# tqfp-sandwich.net
KiCad netlist of a schematic drawn in EAGLE
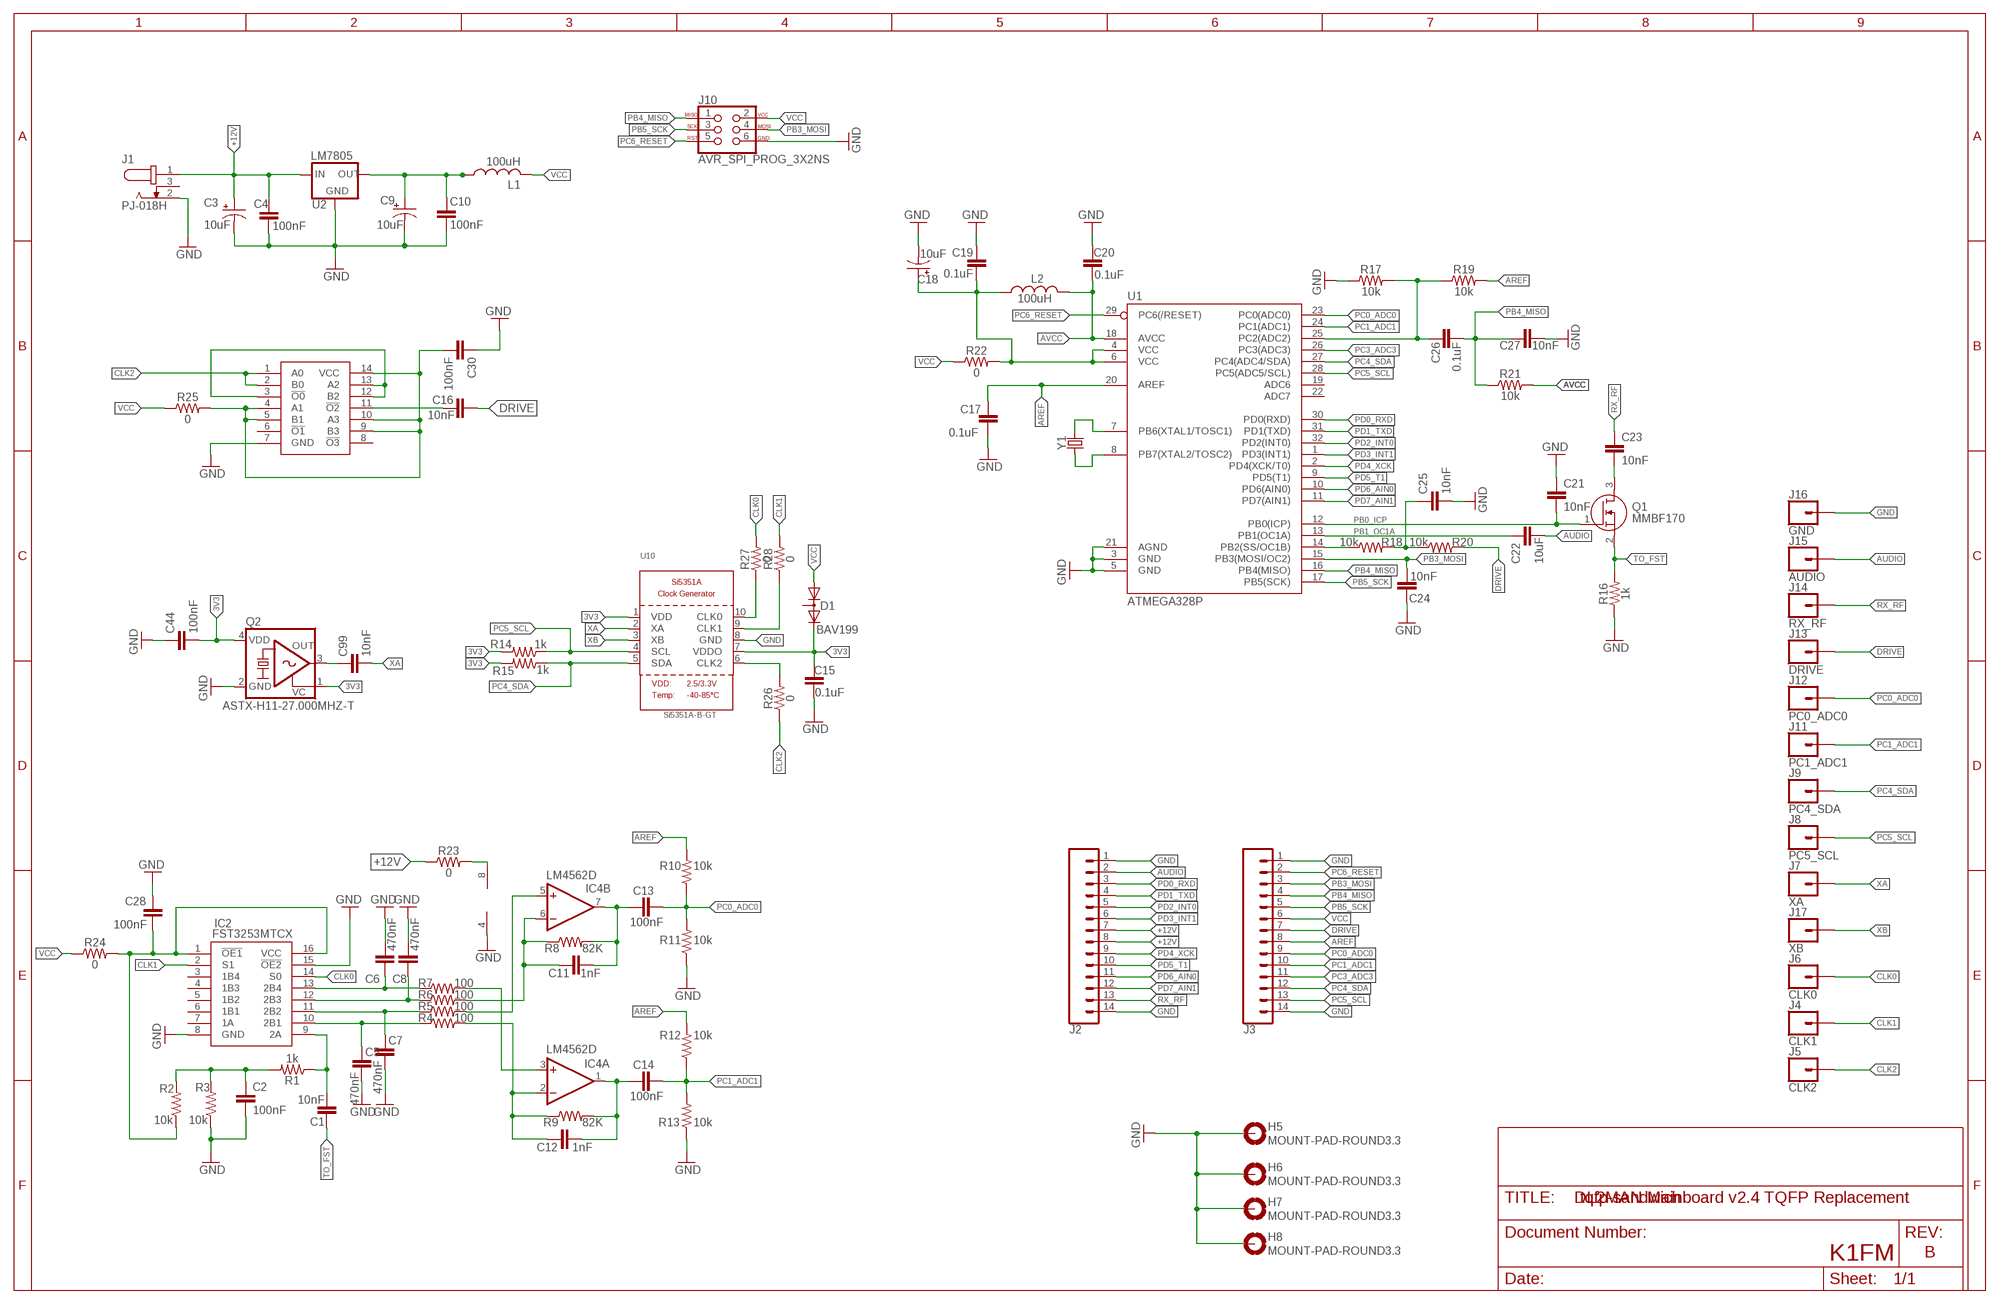
[diagram p0: schematic, sheet 1]

(export (version "E")
  (design (tool "Eeschema 10.0.6"))
  (components
    (comp (ref "C1")
      (value "10nF")
      (footprint "eagle-import:0603")
      (libsource (lib "eagle-import") (part "10NF-0603-50V-10%"))
    )
    (comp (ref "C2")
      (value "100nF")
      (footprint "eagle-import:0603")
      (libsource (lib "eagle-import") (part "10NF-0603-50V-10%"))
    )
    (comp (ref "C3")
      (value "10uF")
      (footprint "eagle-import:EIA3216")
      (libsource (lib "eagle-import") (part "10UF-POLAR-EIA3216-16V-10%(TANT)"))
    )
    (comp (ref "C4")
      (value "100nF")
      (footprint "eagle-import:0603")
      (libsource (lib "eagle-import") (part "10NF-0603-50V-10%"))
    )
    (comp (ref "C5")
      (value "470nF")
      (footprint "eagle-import:0603")
      (libsource (lib "eagle-import") (part "470PF-0603-50V-5%"))
    )
    (comp (ref "C6")
      (value "470nF")
      (footprint "eagle-import:0603")
      (libsource (lib "eagle-import") (part "470PF-0603-50V-5%"))
    )
    (comp (ref "C7")
      (value "470nF")
      (footprint "eagle-import:0603")
      (libsource (lib "eagle-import") (part "470PF-0603-50V-5%"))
    )
    (comp (ref "C8")
      (value "470nF")
      (footprint "eagle-import:0603")
      (libsource (lib "eagle-import") (part "470PF-0603-50V-5%"))
    )
    (comp (ref "C9")
      (value "10uF")
      (footprint "eagle-import:EIA3216")
      (libsource (lib "eagle-import") (part "10UF-POLAR-EIA3216-16V-10%(TANT)"))
    )
    (comp (ref "C10")
      (value "100nF")
      (footprint "eagle-import:0603")
      (libsource (lib "eagle-import") (part "10NF-0603-50V-10%"))
    )
    (comp (ref "C11")
      (value "1nF")
      (footprint "eagle-import:0603")
      (libsource (lib "eagle-import") (part "1.0NF/1000PF-0603-50V-10%"))
    )
    (comp (ref "C12")
      (value "1nF")
      (footprint "eagle-import:0603")
      (libsource (lib "eagle-import") (part "1.0NF/1000PF-0603-50V-10%"))
    )
    (comp (ref "C13")
      (value "100nF")
      (footprint "eagle-import:0603")
      (libsource (lib "eagle-import") (part "10NF-0603-50V-10%"))
    )
    (comp (ref "C14")
      (value "100nF")
      (footprint "eagle-import:0603")
      (libsource (lib "eagle-import") (part "10NF-0603-50V-10%"))
    )
    (comp (ref "C15")
      (value "0.1uF")
      (footprint "eagle-import:0603")
      (libsource (lib "eagle-import") (part "0.1UF-0603-25V-(+80/-20%)"))
    )
    (comp (ref "C16")
      (value "10nF")
      (footprint "eagle-import:0603")
      (libsource (lib "eagle-import") (part "10NF-0603-50V-10%"))
    )
    (comp (ref "C17")
      (value "0.1uF")
      (footprint "eagle-import:0603")
      (libsource (lib "eagle-import") (part "0.1UF-0603-25V-(+80/-20%)"))
    )
    (comp (ref "C18")
      (value "10uF")
      (footprint "eagle-import:EIA3216")
      (libsource (lib "eagle-import") (part "10UF-POLAR-EIA3216-16V-10%(TANT)"))
    )
    (comp (ref "C19")
      (value "0.1uF")
      (footprint "eagle-import:0603")
      (libsource (lib "eagle-import") (part "0.1UF-0603-25V-(+80/-20%)"))
    )
    (comp (ref "C20")
      (value "0.1uF")
      (footprint "eagle-import:0603")
      (libsource (lib "eagle-import") (part "0.1UF-0603-25V-(+80/-20%)"))
    )
    (comp (ref "C21")
      (value "10nF")
      (footprint "eagle-import:0603")
      (libsource (lib "eagle-import") (part "10NF-0603-50V-10%"))
    )
    (comp (ref "C22")
      (value "10uF")
      (footprint "eagle-import:0603")
      (libsource (lib "eagle-import") (part "10UF-0603-6.3V-20%"))
    )
    (comp (ref "C23")
      (value "10nF")
      (footprint "eagle-import:0603")
      (libsource (lib "eagle-import") (part "10NF-0603-50V-10%"))
    )
    (comp (ref "C24")
      (value "10nF")
      (footprint "eagle-import:0603")
      (libsource (lib "eagle-import") (part "10NF-0603-50V-10%"))
    )
    (comp (ref "C25")
      (value "10nF")
      (footprint "eagle-import:0603")
      (libsource (lib "eagle-import") (part "10NF-0603-50V-10%"))
    )
    (comp (ref "C26")
      (value "0.1uF")
      (footprint "eagle-import:0603")
      (libsource (lib "eagle-import") (part "0.1UF-0603-25V-(+80/-20%)"))
    )
    (comp (ref "C27")
      (value "10nF")
      (footprint "eagle-import:0603")
      (libsource (lib "eagle-import") (part "10NF-0603-50V-10%"))
    )
    (comp (ref "C28")
      (value "100nF")
      (footprint "eagle-import:0603")
      (libsource (lib "eagle-import") (part "10NF-0603-50V-10%"))
    )
    (comp (ref "C30")
      (value "100nF")
      (footprint "eagle-import:0603")
      (libsource (lib "eagle-import") (part "10NF-0603-50V-10%"))
    )
    (comp (ref "C44")
      (value "100nF")
      (footprint "eagle-import:0603")
      (libsource (lib "eagle-import") (part "10NF-0603-50V-10%"))
    )
    (comp (ref "C99")
      (value "10nF")
      (footprint "eagle-import:0603")
      (libsource (lib "eagle-import") (part "10NF-0603-50V-10%"))
    )
    (comp (ref "D1")
      (value "BAV199")
      (footprint "eagle-import:SOT23")
      (libsource (lib "eagle-import") (part "BAV199"))
    )
    (comp (ref "H5")
      (value "MOUNT-PAD-ROUND3.3")
      (footprint "eagle-import:3,3-PAD")
      (libsource (lib "eagle-import") (part "MOUNT-PAD-ROUND3.3"))
    )
    (comp (ref "H6")
      (value "MOUNT-PAD-ROUND3.3")
      (footprint "eagle-import:3,3-PAD")
      (libsource (lib "eagle-import") (part "MOUNT-PAD-ROUND3.3"))
    )
    (comp (ref "H7")
      (value "MOUNT-PAD-ROUND3.3")
      (footprint "eagle-import:3,3-PAD")
      (libsource (lib "eagle-import") (part "MOUNT-PAD-ROUND3.3"))
    )
    (comp (ref "H8")
      (value "MOUNT-PAD-ROUND3.3")
      (footprint "eagle-import:3,3-PAD")
      (libsource (lib "eagle-import") (part "MOUNT-PAD-ROUND3.3"))
    )
    (comp (ref "IC2")
      (value "FST3253MTCX")
      (footprint "eagle-import:SOP65P640X110-16N")
      (fields (field (name "MOUSER_PART_NUMBER") "512-FST3253MTCX"))
      (libsource (lib "eagle-import") (part "FST3253MTCX"))
    )
    (comp (ref "IC3")
      (value "74ACT00MTC")
      (footprint "eagle-import:SOP65P640X120-14N")
      (fields (field (name "MOUSER_PART_NUMBER") "512-74ACT00MTC"))
      (libsource (lib "eagle-import") (part "74ACT00MTC"))
    )
    (comp (ref "IC4")
      (value "LM4562D")
      (footprint "eagle-import:SO08")
      (libsource (lib "eagle-import") (part "LM4562D"))
    )
    (comp (ref "J1")
      (value "PJ-018H")
      (footprint "eagle-import:CUI_PJ-018H")
      (fields (field (name "MANUFACTURER") "CUI INC"))
      (libsource (lib "eagle-import") (part "PJ-018H"))
    )
    (comp (ref "J2")
      (value "CONN_14")
      (footprint "eagle-import:1X14")
      (libsource (lib "eagle-import") (part "CONN_14"))
    )
    (comp (ref "J3")
      (value "CONN_14")
      (footprint "eagle-import:1X14")
      (libsource (lib "eagle-import") (part "CONN_14"))
    )
    (comp (ref "J4")
      (value "CLK1")
      (footprint "eagle-import:1X01_LONGPAD")
      (libsource (lib "eagle-import") (part "CONN_01PTH_LONGPAD"))
    )
    (comp (ref "J5")
      (value "CLK2")
      (footprint "eagle-import:1X01_LONGPAD")
      (libsource (lib "eagle-import") (part "CONN_01PTH_LONGPAD"))
    )
    (comp (ref "J6")
      (value "CLK0")
      (footprint "eagle-import:1X01_LONGPAD")
      (libsource (lib "eagle-import") (part "CONN_01PTH_LONGPAD"))
    )
    (comp (ref "J7")
      (value "XA")
      (footprint "eagle-import:1X01_LONGPAD")
      (libsource (lib "eagle-import") (part "CONN_01PTH_LONGPAD"))
    )
    (comp (ref "J8")
      (value "PC5_SCL")
      (footprint "eagle-import:1X01_LONGPAD")
      (libsource (lib "eagle-import") (part "CONN_01PTH_LONGPAD"))
    )
    (comp (ref "J9")
      (value "PC4_SDA")
      (footprint "eagle-import:1X01_LONGPAD")
      (libsource (lib "eagle-import") (part "CONN_01PTH_LONGPAD"))
    )
    (comp (ref "J10")
      (value "AVR_SPI_PROG_3X2NS")
      (footprint "eagle-import:2X3-NS")
      (libsource (lib "eagle-import") (part "AVR_SPI_PROG_3X2NS"))
    )
    (comp (ref "J11")
      (value "PC1_ADC1")
      (footprint "eagle-import:1X01_LONGPAD")
      (libsource (lib "eagle-import") (part "CONN_01PTH_LONGPAD"))
    )
    (comp (ref "J12")
      (value "PC0_ADC0")
      (footprint "eagle-import:1X01_LONGPAD")
      (libsource (lib "eagle-import") (part "CONN_01PTH_LONGPAD"))
    )
    (comp (ref "J13")
      (value "DRIVE")
      (footprint "eagle-import:1X01_LONGPAD")
      (libsource (lib "eagle-import") (part "CONN_01PTH_LONGPAD"))
    )
    (comp (ref "J14")
      (value "RX_RF")
      (footprint "eagle-import:1X01_LONGPAD")
      (libsource (lib "eagle-import") (part "CONN_01PTH_LONGPAD"))
    )
    (comp (ref "J15")
      (value "AUDIO")
      (footprint "eagle-import:1X01_LONGPAD")
      (libsource (lib "eagle-import") (part "CONN_01PTH_LONGPAD"))
    )
    (comp (ref "J16")
      (value "GND")
      (footprint "eagle-import:1X01_LONGPAD")
      (libsource (lib "eagle-import") (part "CONN_01PTH_LONGPAD"))
    )
    (comp (ref "J17")
      (value "XB")
      (footprint "eagle-import:1X01_LONGPAD")
      (libsource (lib "eagle-import") (part "CONN_01PTH_LONGPAD"))
    )
    (comp (ref "L1")
      (value "100uH")
      (footprint "eagle-import:RESC0805_L")
      (libsource (lib "eagle-import") (part "INDUCTOR_0805_L"))
    )
    (comp (ref "L2")
      (value "100uH")
      (footprint "eagle-import:RESC0805_L")
      (libsource (lib "eagle-import") (part "INDUCTOR_0805_L"))
    )
    (comp (ref "Q1")
      (value "MMBF170")
      (footprint "eagle-import:SOT96P237X111-3N")
      (fields (field (name "MOUSER_PART_NUMBER") "512-MMBF170"))
      (libsource (lib "eagle-import") (part "MMBF170"))
    )
    (comp (ref "Q2")
      (value "ASTX-H11-27.000MHZ-T")
      (footprint "eagle-import:3.2X2.5_KXO-84")
      (libsource (lib "eagle-import") (part "KXO-VCXO-SINE-84"))
    )
    (comp (ref "R1")
      (value "1k")
      (footprint "eagle-import:0603")
      (libsource (lib "eagle-import") (part "1KOHM-0603-1/10W-1%"))
    )
    (comp (ref "R2")
      (value "10k")
      (footprint "eagle-import:0603")
      (libsource (lib "eagle-import") (part "10KOHM-0603-1/10W-1%"))
    )
    (comp (ref "R3")
      (value "10k")
      (footprint "eagle-import:0603")
      (libsource (lib "eagle-import") (part "10KOHM-0603-1/10W-1%"))
    )
    (comp (ref "R4")
      (value "100")
      (footprint "eagle-import:0603")
      (libsource (lib "eagle-import") (part "100OHM-0603-1/4W-5%"))
    )
    (comp (ref "R5")
      (value "100")
      (footprint "eagle-import:0603")
      (libsource (lib "eagle-import") (part "100OHM-0603-1/4W-5%"))
    )
    (comp (ref "R6")
      (value "100")
      (footprint "eagle-import:0603")
      (libsource (lib "eagle-import") (part "100OHM-0603-1/4W-5%"))
    )
    (comp (ref "R7")
      (value "100")
      (footprint "eagle-import:0603")
      (libsource (lib "eagle-import") (part "100OHM-0603-1/4W-5%"))
    )
    (comp (ref "R8")
      (value "82K")
      (footprint "eagle-import:0603")
      (libsource (lib "eagle-import") (part "82OHM-0603-1/10W-1%"))
    )
    (comp (ref "R9")
      (value "82K")
      (footprint "eagle-import:0603")
      (libsource (lib "eagle-import") (part "82OHM-0603-1/10W-1%"))
    )
    (comp (ref "R10")
      (value "10k")
      (footprint "eagle-import:0603")
      (libsource (lib "eagle-import") (part "10KOHM-0603-1/10W-1%"))
    )
    (comp (ref "R11")
      (value "10k")
      (footprint "eagle-import:0603")
      (libsource (lib "eagle-import") (part "10KOHM-0603-1/10W-1%"))
    )
    (comp (ref "R12")
      (value "10k")
      (footprint "eagle-import:0603")
      (libsource (lib "eagle-import") (part "10KOHM-0603-1/10W-1%"))
    )
    (comp (ref "R13")
      (value "10k")
      (footprint "eagle-import:0603")
      (libsource (lib "eagle-import") (part "10KOHM-0603-1/10W-1%"))
    )
    (comp (ref "R14")
      (value "1k")
      (footprint "eagle-import:0603")
      (libsource (lib "eagle-import") (part "1KOHM-0603-1/10W-1%"))
    )
    (comp (ref "R15")
      (value "1k")
      (footprint "eagle-import:0603")
      (libsource (lib "eagle-import") (part "1KOHM-0603-1/10W-1%"))
    )
    (comp (ref "R16")
      (value "1k")
      (footprint "eagle-import:0603")
      (libsource (lib "eagle-import") (part "1KOHM-0603-1/10W-1%"))
    )
    (comp (ref "R17")
      (value "10k")
      (footprint "eagle-import:0603")
      (libsource (lib "eagle-import") (part "10KOHM-0603-1/10W-1%"))
    )
    (comp (ref "R18")
      (value "10k")
      (footprint "eagle-import:0603")
      (libsource (lib "eagle-import") (part "10KOHM-0603-1/10W-1%"))
    )
    (comp (ref "R19")
      (value "10k")
      (footprint "eagle-import:0603")
      (libsource (lib "eagle-import") (part "10KOHM-0603-1/10W-1%"))
    )
    (comp (ref "R20")
      (value "10k")
      (footprint "eagle-import:0603")
      (libsource (lib "eagle-import") (part "10KOHM-0603-1/10W-1%"))
    )
    (comp (ref "R21")
      (value "10k")
      (footprint "eagle-import:0603")
      (libsource (lib "eagle-import") (part "10KOHM-0603-1/10W-1%"))
    )
    (comp (ref "R22")
      (value "0")
      (footprint "eagle-import:0603")
      (libsource (lib "eagle-import") (part "0OHM-0603-1/10W-5%"))
    )
    (comp (ref "R23")
      (value "0")
      (footprint "eagle-import:0603")
      (libsource (lib "eagle-import") (part "0OHM-0603-1/10W-5%"))
    )
    (comp (ref "R24")
      (value "0")
      (footprint "eagle-import:0603")
      (libsource (lib "eagle-import") (part "0OHM-0603-1/10W-5%"))
    )
    (comp (ref "R25")
      (value "0")
      (footprint "eagle-import:0603")
      (libsource (lib "eagle-import") (part "0OHM-0603-1/10W-5%"))
    )
    (comp (ref "R26")
      (value "0")
      (footprint "eagle-import:0603")
      (libsource (lib "eagle-import") (part "0OHM-0603-1/10W-5%"))
    )
    (comp (ref "R27")
      (value "0")
      (footprint "eagle-import:0603")
      (libsource (lib "eagle-import") (part "0OHM-0603-1/10W-5%"))
    )
    (comp (ref "R28")
      (value "0")
      (footprint "eagle-import:0603")
      (libsource (lib "eagle-import") (part "0OHM-0603-1/10W-5%"))
    )
    (comp (ref "U1")
      (value "ATMEGA328P")
      (footprint "eagle-import:TQFP32-08")
      (libsource (lib "eagle-import") (part "ATMEGA328P_TQFP"))
    )
    (comp (ref "U2")
      (value "LM7805")
      (footprint "eagle-import:TO-252")
      (libsource (lib "eagle-import") (part "V_REG_78XX7812"))
    )
    (comp (ref "U10")
      (value "Si5351A-B-GT")
      (footprint "eagle-import:MSOP10")
      (libsource (lib "eagle-import") (part "SI5351A"))
    )
    (comp (ref "Y1")
      (value "CRYSTALSMD-5X3.2-2PAD")
      (footprint "eagle-import:CRYSTAL-SMD-5X3.2-2PAD")
      (libsource (lib "eagle-import") (part "CRYSTALSMD-5X3.2-2PAD"))
    )
  )
  (nets
    (net (code "1") (name "+12V") (class "Default")
      (node (ref "C3") (pin "+") (pinfunction "+_+") (pintype "passive"))
      (node (ref "C4") (pin "2") (pinfunction "2_2") (pintype "passive"))
      (node (ref "J1") (pin "1") (pinfunction "1_1") (pintype "passive"))
      (node (ref "J2") (pin "7") (pinfunction "7_7") (pintype "passive"))
      (node (ref "J2") (pin "8") (pinfunction "8_8") (pintype "passive"))
      (node (ref "R23") (pin "1") (pinfunction "1_1") (pintype "passive"))
      (node (ref "U2") (pin "1") (pinfunction "IN_1") (pintype "input"))
    )
    (net (code "2") (name "/PB0_ICP") (class "Default")
      (node (ref "C21") (pin "2") (pinfunction "2_2") (pintype "passive"))
      (node (ref "Q1") (pin "1") (pinfunction "G_1") (pintype "bidirectional"))
      (node (ref "U1") (pin "12") (pinfunction "PB0(ICP)_12") (pintype "bidirectional"))
    )
    (net (code "3") (name "/PB1_OC1A") (class "Default")
      (node (ref "C22") (pin "1") (pinfunction "1_1") (pintype "passive"))
      (node (ref "U1") (pin "13") (pinfunction "PB1(OC1A)_13") (pintype "bidirectional"))
    )
    (net (code "4") (name "3V3") (class "Default")
      (node (ref "C15") (pin "2") (pinfunction "2_2") (pintype "passive"))
      (node (ref "C44") (pin "2") (pinfunction "2_2") (pintype "passive"))
      (node (ref "D1") (pin "2") (pinfunction "C_2") (pintype "passive"))
      (node (ref "Q2") (pin "1") (pinfunction "VC_1") (pintype "input"))
      (node (ref "Q2") (pin "4") (pinfunction "VDD_4") (pintype "power_in"))
      (node (ref "R14") (pin "2") (pinfunction "2_2") (pintype "passive"))
      (node (ref "R15") (pin "2") (pinfunction "2_2") (pintype "passive"))
      (node (ref "U10") (pin "1") (pinfunction "VDD_1") (pintype "power_in"))
      (node (ref "U10") (pin "7") (pinfunction "VDDO_7") (pintype "power_in"))
    )
    (net (code "5") (name "AREF") (class "Default")
      (node (ref "C17") (pin "2") (pinfunction "2_2") (pintype "passive"))
      (node (ref "J3") (pin "8") (pinfunction "8_8") (pintype "passive"))
      (node (ref "R10") (pin "2") (pinfunction "2_2") (pintype "passive"))
      (node (ref "R12") (pin "2") (pinfunction "2_2") (pintype "passive"))
      (node (ref "R19") (pin "2") (pinfunction "2_2") (pintype "passive"))
      (node (ref "U1") (pin "20") (pinfunction "AREF_20") (pintype "bidirectional"))
    )
    (net (code "6") (name "AUDIO") (class "Default")
      (node (ref "C22") (pin "2") (pinfunction "2_2") (pintype "passive"))
      (node (ref "J15") (pin "1") (pinfunction "1_1") (pintype "passive"))
      (node (ref "J2") (pin "2") (pinfunction "2_2") (pintype "passive"))
    )
    (net (code "7") (name "AVCC") (class "Default")
      (node (ref "C20") (pin "1") (pinfunction "1_1") (pintype "passive"))
      (node (ref "L2") (pin "2") (pinfunction "2_2") (pintype "passive"))
      (node (ref "R21") (pin "2") (pinfunction "2_2") (pintype "passive"))
      (node (ref "U1") (pin "18") (pinfunction "AVCC_18") (pintype "bidirectional"))
    )
    (net (code "8") (name "CLK0") (class "Default")
      (node (ref "IC2") (pin "14") (pinfunction "S0_14") (pintype "bidirectional"))
      (node (ref "J6") (pin "1") (pinfunction "1_1") (pintype "passive"))
      (node (ref "R27") (pin "2") (pinfunction "2_2") (pintype "passive"))
    )
    (net (code "9") (name "CLK1") (class "Default")
      (node (ref "IC2") (pin "2") (pinfunction "S1_2") (pintype "bidirectional"))
      (node (ref "J4") (pin "1") (pinfunction "1_1") (pintype "passive"))
      (node (ref "R28") (pin "2") (pinfunction "2_2") (pintype "passive"))
    )
    (net (code "10") (name "CLK2") (class "Default")
      (node (ref "IC3") (pin "1") (pinfunction "A0_1") (pintype "bidirectional"))
      (node (ref "IC3") (pin "2") (pinfunction "B0_2") (pintype "bidirectional"))
      (node (ref "J5") (pin "1") (pinfunction "1_1") (pintype "passive"))
      (node (ref "R26") (pin "1") (pinfunction "1_1") (pintype "passive"))
    )
    (net (code "11") (name "DRIVE") (class "Default")
      (node (ref "C16") (pin "2") (pinfunction "2_2") (pintype "passive"))
      (node (ref "J13") (pin "1") (pinfunction "1_1") (pintype "passive"))
      (node (ref "J3") (pin "7") (pinfunction "7_7") (pintype "passive"))
      (node (ref "R20") (pin "2") (pinfunction "2_2") (pintype "passive"))
    )
    (net (code "12") (name "GND") (class "Default")
      (node (ref "C10") (pin "1") (pinfunction "1_1") (pintype "passive"))
      (node (ref "C15") (pin "1") (pinfunction "1_1") (pintype "passive"))
      (node (ref "C17") (pin "1") (pinfunction "1_1") (pintype "passive"))
      (node (ref "C18") (pin "-") (pinfunction "-_-") (pintype "passive"))
      (node (ref "C19") (pin "2") (pinfunction "2_2") (pintype "passive"))
      (node (ref "C2") (pin "2") (pinfunction "2_2") (pintype "passive"))
      (node (ref "C20") (pin "2") (pinfunction "2_2") (pintype "passive"))
      (node (ref "C21") (pin "1") (pinfunction "1_1") (pintype "passive"))
      (node (ref "C24") (pin "1") (pinfunction "1_1") (pintype "passive"))
      (node (ref "C25") (pin "2") (pinfunction "2_2") (pintype "passive"))
      (node (ref "C27") (pin "2") (pinfunction "2_2") (pintype "passive"))
      (node (ref "C28") (pin "1") (pinfunction "1_1") (pintype "passive"))
      (node (ref "C3") (pin "-") (pinfunction "-_-") (pintype "passive"))
      (node (ref "C30") (pin "1") (pinfunction "1_1") (pintype "passive"))
      (node (ref "C4") (pin "1") (pinfunction "1_1") (pintype "passive"))
      (node (ref "C44") (pin "1") (pinfunction "1_1") (pintype "passive"))
      (node (ref "C5") (pin "2") (pinfunction "2_2") (pintype "passive"))
      (node (ref "C6") (pin "2") (pinfunction "2_2") (pintype "passive"))
      (node (ref "C7") (pin "2") (pinfunction "2_2") (pintype "passive"))
      (node (ref "C8") (pin "2") (pinfunction "2_2") (pintype "passive"))
      (node (ref "C9") (pin "-") (pinfunction "-_-") (pintype "passive"))
      (node (ref "H5") (pin "B3,3") (pinfunction "MOUNT_B3,3") (pintype "passive"))
      (node (ref "H6") (pin "B3,3") (pinfunction "MOUNT_B3,3") (pintype "passive"))
      (node (ref "H7") (pin "B3,3") (pinfunction "MOUNT_B3,3") (pintype "passive"))
      (node (ref "H8") (pin "B3,3") (pinfunction "MOUNT_B3,3") (pintype "passive"))
      (node (ref "IC2") (pin "15") (pinfunction "~{OE2}_15") (pintype "bidirectional"))
      (node (ref "IC2") (pin "8") (pinfunction "GND_8") (pintype "power_in"))
      (node (ref "IC3") (pin "7") (pinfunction "GND_7") (pintype "bidirectional"))
      (node (ref "IC4") (pin "4") (pinfunction "V-_4") (pintype "power_in"))
      (node (ref "J1") (pin "2") (pinfunction "2_2") (pintype "passive"))
      (node (ref "J10") (pin "6") (pinfunction "6_6") (pintype "passive"))
      (node (ref "J16") (pin "1") (pinfunction "1_1") (pintype "passive"))
      (node (ref "J2") (pin "1") (pinfunction "1_1") (pintype "passive"))
      (node (ref "J2") (pin "14") (pinfunction "14_14") (pintype "passive"))
      (node (ref "J3") (pin "1") (pinfunction "1_1") (pintype "passive"))
      (node (ref "J3") (pin "14") (pinfunction "14_14") (pintype "passive"))
      (node (ref "Q2") (pin "2") (pinfunction "GND_2") (pintype "power_in"))
      (node (ref "R11") (pin "1") (pinfunction "1_1") (pintype "passive"))
      (node (ref "R13") (pin "1") (pinfunction "1_1") (pintype "passive"))
      (node (ref "R16") (pin "1") (pinfunction "1_1") (pintype "passive"))
      (node (ref "R17") (pin "1") (pinfunction "1_1") (pintype "passive"))
      (node (ref "R3") (pin "1") (pinfunction "1_1") (pintype "passive"))
      (node (ref "U1") (pin "21") (pinfunction "AGND_21") (pintype "bidirectional"))
      (node (ref "U1") (pin "3") (pinfunction "GND_3") (pintype "bidirectional"))
      (node (ref "U1") (pin "5") (pinfunction "GND_5") (pintype "bidirectional"))
      (node (ref "U10") (pin "8") (pinfunction "GND_8") (pintype "power_in"))
      (node (ref "U2") (pin "3") (pinfunction "GND_3") (pintype "input"))
    )
    (net (code "13") (name "Net-(C2-Pad1)") (class "Default")
      (node (ref "C2") (pin "1") (pinfunction "1_1") (pintype "passive"))
      (node (ref "R1") (pin "2") (pinfunction "2_2") (pintype "passive"))
      (node (ref "R2") (pin "2") (pinfunction "2_2") (pintype "passive"))
      (node (ref "R3") (pin "2") (pinfunction "2_2") (pintype "passive"))
    )
    (net (code "14") (name "Net-(C18-Pad+)") (class "Default")
      (node (ref "C18") (pin "+") (pinfunction "+_+") (pintype "passive"))
      (node (ref "C19") (pin "1") (pinfunction "1_1") (pintype "passive"))
      (node (ref "L2") (pin "1") (pinfunction "1_1") (pintype "passive"))
      (node (ref "R22") (pin "2") (pinfunction "2_2") (pintype "passive"))
      (node (ref "U1") (pin "4") (pinfunction "VCC_4") (pintype "bidirectional"))
      (node (ref "U1") (pin "6") (pinfunction "VCC_6") (pintype "bidirectional"))
    )
    (net (code "15") (name "Net-(C25-Pad1)") (class "Default")
      (node (ref "C25") (pin "1") (pinfunction "1_1") (pintype "passive"))
      (node (ref "R18") (pin "2") (pinfunction "2_2") (pintype "passive"))
      (node (ref "R20") (pin "1") (pinfunction "1_1") (pintype "passive"))
    )
    (net (code "16") (name "Net-(IC2-2A)") (class "Default")
      (node (ref "C1") (pin "2") (pinfunction "2_2") (pintype "passive"))
      (node (ref "IC2") (pin "9") (pinfunction "2A_9") (pintype "bidirectional"))
      (node (ref "R1") (pin "1") (pinfunction "1_1") (pintype "passive"))
    )
    (net (code "17") (name "Net-(IC2-2B1)") (class "Default")
      (node (ref "C5") (pin "1") (pinfunction "1_1") (pintype "passive"))
      (node (ref "IC2") (pin "10") (pinfunction "2B1_10") (pintype "bidirectional"))
      (node (ref "R4") (pin "1") (pinfunction "1_1") (pintype "passive"))
    )
    (net (code "18") (name "Net-(IC2-2B2)") (class "Default")
      (node (ref "C7") (pin "1") (pinfunction "1_1") (pintype "passive"))
      (node (ref "IC2") (pin "11") (pinfunction "2B2_11") (pintype "bidirectional"))
      (node (ref "R5") (pin "1") (pinfunction "1_1") (pintype "passive"))
    )
    (net (code "19") (name "Net-(IC2-2B3)") (class "Default")
      (node (ref "C8") (pin "1") (pinfunction "1_1") (pintype "passive"))
      (node (ref "IC2") (pin "12") (pinfunction "2B3_12") (pintype "bidirectional"))
      (node (ref "R6") (pin "1") (pinfunction "1_1") (pintype "passive"))
    )
    (net (code "20") (name "Net-(IC2-2B4)") (class "Default")
      (node (ref "C6") (pin "1") (pinfunction "1_1") (pintype "passive"))
      (node (ref "IC2") (pin "13") (pinfunction "2B4_13") (pintype "bidirectional"))
      (node (ref "R7") (pin "1") (pinfunction "1_1") (pintype "passive"))
    )
    (net (code "21") (name "Net-(IC2-VCC)") (class "Default")
      (node (ref "C28") (pin "2") (pinfunction "2_2") (pintype "passive"))
      (node (ref "IC2") (pin "1") (pinfunction "~{OE1}_1") (pintype "bidirectional"))
      (node (ref "IC2") (pin "16") (pinfunction "VCC_16") (pintype "power_in"))
      (node (ref "R2") (pin "1") (pinfunction "1_1") (pintype "passive"))
      (node (ref "R24") (pin "2") (pinfunction "2_2") (pintype "passive"))
    )
    (net (code "22") (name "Net-(IC3-A1)") (class "Default")
      (node (ref "C30") (pin "2") (pinfunction "2_2") (pintype "passive"))
      (node (ref "IC3") (pin "10") (pinfunction "A3_10") (pintype "bidirectional"))
      (node (ref "IC3") (pin "14") (pinfunction "VCC_14") (pintype "bidirectional"))
      (node (ref "IC3") (pin "4") (pinfunction "A1_4") (pintype "bidirectional"))
      (node (ref "IC3") (pin "5") (pinfunction "B1_5") (pintype "bidirectional"))
      (node (ref "IC3") (pin "9") (pinfunction "B3_9") (pintype "bidirectional"))
      (node (ref "R25") (pin "2") (pinfunction "2_2") (pintype "passive"))
    )
    (net (code "23") (name "Net-(IC3-A2)") (class "Default")
      (node (ref "IC3") (pin "12") (pinfunction "B2_12") (pintype "bidirectional"))
      (node (ref "IC3") (pin "13") (pinfunction "A2_13") (pintype "bidirectional"))
      (node (ref "IC3") (pin "3") (pinfunction "~{O0}_3") (pintype "bidirectional"))
    )
    (net (code "24") (name "Net-(IC3-~{O2})") (class "Default")
      (node (ref "C16") (pin "1") (pinfunction "1_1") (pintype "passive"))
      (node (ref "IC3") (pin "11") (pinfunction "~{O2}_11") (pintype "bidirectional"))
    )
    (net (code "25") (name "Net-(IC4A-+IN)") (class "Default")
      (node (ref "IC4") (pin "3") (pinfunction "+IN_3") (pintype "input"))
      (node (ref "R7") (pin "2") (pinfunction "2_2") (pintype "passive"))
    )
    (net (code "26") (name "Net-(IC4A--IN)") (class "Default")
      (node (ref "C12") (pin "1") (pinfunction "1_1") (pintype "passive"))
      (node (ref "IC4") (pin "2") (pinfunction "-IN_2") (pintype "input"))
      (node (ref "R4") (pin "2") (pinfunction "2_2") (pintype "passive"))
      (node (ref "R9") (pin "1") (pinfunction "1_1") (pintype "passive"))
    )
    (net (code "27") (name "Net-(IC4A-OUT)") (class "Default")
      (node (ref "C12") (pin "2") (pinfunction "2_2") (pintype "passive"))
      (node (ref "C14") (pin "1") (pinfunction "1_1") (pintype "passive"))
      (node (ref "IC4") (pin "1") (pinfunction "OUT_1") (pintype "output"))
      (node (ref "R9") (pin "2") (pinfunction "2_2") (pintype "passive"))
    )
    (net (code "28") (name "Net-(IC4B-+IN)") (class "Default")
      (node (ref "IC4") (pin "5") (pinfunction "+IN_5") (pintype "input"))
      (node (ref "R5") (pin "2") (pinfunction "2_2") (pintype "passive"))
    )
    (net (code "29") (name "Net-(IC4B--IN)") (class "Default")
      (node (ref "C11") (pin "1") (pinfunction "1_1") (pintype "passive"))
      (node (ref "IC4") (pin "6") (pinfunction "-IN_6") (pintype "input"))
      (node (ref "R6") (pin "2") (pinfunction "2_2") (pintype "passive"))
      (node (ref "R8") (pin "1") (pinfunction "1_1") (pintype "passive"))
    )
    (net (code "30") (name "Net-(IC4B-OUT)") (class "Default")
      (node (ref "C11") (pin "2") (pinfunction "2_2") (pintype "passive"))
      (node (ref "C13") (pin "1") (pinfunction "1_1") (pintype "passive"))
      (node (ref "IC4") (pin "7") (pinfunction "OUT_7") (pintype "output"))
      (node (ref "R8") (pin "2") (pinfunction "2_2") (pintype "passive"))
    )
    (net (code "31") (name "Net-(IC4C-V+)") (class "Default")
      (node (ref "IC4") (pin "8") (pinfunction "V+_8") (pintype "power_in"))
      (node (ref "R23") (pin "2") (pinfunction "2_2") (pintype "passive"))
    )
    (net (code "32") (name "Net-(Q1-D)") (class "Default")
      (node (ref "C23") (pin "2") (pinfunction "2_2") (pintype "passive"))
      (node (ref "Q1") (pin "3") (pinfunction "D_3") (pintype "bidirectional"))
    )
    (net (code "33") (name "Net-(Q2-OUT)") (class "Default")
      (node (ref "C99") (pin "1") (pinfunction "1_1") (pintype "passive"))
      (node (ref "Q2") (pin "3") (pinfunction "OUT_3") (pintype "output"))
    )
    (net (code "34") (name "Net-(U1-PB2(SS{slash}OC1B))") (class "Default")
      (node (ref "R18") (pin "1") (pinfunction "1_1") (pintype "passive"))
      (node (ref "U1") (pin "14") (pinfunction "PB2(SS/OC1B)_14") (pintype "bidirectional"))
    )
    (net (code "35") (name "Net-(U1-PB6(XTAL1{slash}TOSC1))") (class "Default")
      (node (ref "U1") (pin "7") (pinfunction "PB6(XTAL1/TOSC1)_7") (pintype "bidirectional"))
      (node (ref "Y1") (pin "P$2") (pinfunction "2_P$2") (pintype "passive"))
    )
    (net (code "36") (name "Net-(U1-PB7(XTAL2{slash}TOSC2))") (class "Default")
      (node (ref "U1") (pin "8") (pinfunction "PB7(XTAL2/TOSC2)_8") (pintype "bidirectional"))
      (node (ref "Y1") (pin "P$1") (pinfunction "1_P$1") (pintype "passive"))
    )
    (net (code "37") (name "Net-(U1-PC2(ADC2))") (class "Default")
      (node (ref "C26") (pin "2") (pinfunction "2_2") (pintype "passive"))
      (node (ref "R17") (pin "2") (pinfunction "2_2") (pintype "passive"))
      (node (ref "R19") (pin "1") (pinfunction "1_1") (pintype "passive"))
      (node (ref "U1") (pin "25") (pinfunction "PC2(ADC2)_25") (pintype "bidirectional"))
    )
    (net (code "38") (name "Net-(U2-OUT)") (class "Default")
      (node (ref "C10") (pin "2") (pinfunction "2_2") (pintype "passive"))
      (node (ref "C9") (pin "+") (pinfunction "+_+") (pintype "passive"))
      (node (ref "L1") (pin "1") (pinfunction "1_1") (pintype "passive"))
      (node (ref "U2") (pin "2") (pinfunction "OUT_2") (pintype "passive"))
    )
    (net (code "39") (name "Net-(U10-CLK0)") (class "Default")
      (node (ref "R27") (pin "1") (pinfunction "1_1") (pintype "passive"))
      (node (ref "U10") (pin "10") (pinfunction "CLK0_10") (pintype "output"))
    )
    (net (code "40") (name "Net-(U10-CLK1)") (class "Default")
      (node (ref "R28") (pin "1") (pinfunction "1_1") (pintype "passive"))
      (node (ref "U10") (pin "9") (pinfunction "CLK1_9") (pintype "output"))
    )
    (net (code "41") (name "Net-(U10-CLK2)") (class "Default")
      (node (ref "R26") (pin "2") (pinfunction "2_2") (pintype "passive"))
      (node (ref "U10") (pin "6") (pinfunction "CLK2_6") (pintype "output"))
    )
    (net (code "42") (name "PB3_MOSI") (class "Default")
      (node (ref "C24") (pin "2") (pinfunction "2_2") (pintype "passive"))
      (node (ref "J10") (pin "4") (pinfunction "4_4") (pintype "passive"))
      (node (ref "J3") (pin "3") (pinfunction "3_3") (pintype "passive"))
      (node (ref "U1") (pin "15") (pinfunction "PB3(MOSI/OC2)_15") (pintype "bidirectional"))
    )
    (net (code "43") (name "PB4_MISO") (class "Default")
      (node (ref "C26") (pin "1") (pinfunction "1_1") (pintype "passive"))
      (node (ref "C27") (pin "1") (pinfunction "1_1") (pintype "passive"))
      (node (ref "J10") (pin "1") (pinfunction "1_1") (pintype "passive"))
      (node (ref "J3") (pin "4") (pinfunction "4_4") (pintype "passive"))
      (node (ref "R21") (pin "1") (pinfunction "1_1") (pintype "passive"))
      (node (ref "U1") (pin "16") (pinfunction "PB4(MISO)_16") (pintype "bidirectional"))
    )
    (net (code "44") (name "PB5_SCK") (class "Default")
      (node (ref "J10") (pin "3") (pinfunction "3_3") (pintype "passive"))
      (node (ref "J3") (pin "5") (pinfunction "5_5") (pintype "passive"))
      (node (ref "U1") (pin "17") (pinfunction "PB5(SCK)_17") (pintype "bidirectional"))
    )
    (net (code "45") (name "PC0_ADC0") (class "Default")
      (node (ref "C13") (pin "2") (pinfunction "2_2") (pintype "passive"))
      (node (ref "J12") (pin "1") (pinfunction "1_1") (pintype "passive"))
      (node (ref "J3") (pin "9") (pinfunction "9_9") (pintype "passive"))
      (node (ref "R10") (pin "1") (pinfunction "1_1") (pintype "passive"))
      (node (ref "R11") (pin "2") (pinfunction "2_2") (pintype "passive"))
      (node (ref "U1") (pin "23") (pinfunction "PC0(ADC0)_23") (pintype "bidirectional"))
    )
    (net (code "46") (name "PC1_ADC1") (class "Default")
      (node (ref "C14") (pin "2") (pinfunction "2_2") (pintype "passive"))
      (node (ref "J11") (pin "1") (pinfunction "1_1") (pintype "passive"))
      (node (ref "J3") (pin "10") (pinfunction "10_10") (pintype "passive"))
      (node (ref "R12") (pin "1") (pinfunction "1_1") (pintype "passive"))
      (node (ref "R13") (pin "2") (pinfunction "2_2") (pintype "passive"))
      (node (ref "U1") (pin "24") (pinfunction "PC1(ADC1)_24") (pintype "bidirectional"))
    )
    (net (code "47") (name "PC3_ADC3") (class "Default")
      (node (ref "J3") (pin "11") (pinfunction "11_11") (pintype "passive"))
      (node (ref "U1") (pin "26") (pinfunction "PC3(ADC3)_26") (pintype "bidirectional"))
    )
    (net (code "48") (name "PC4_SDA") (class "Default")
      (node (ref "J3") (pin "12") (pinfunction "12_12") (pintype "passive"))
      (node (ref "J9") (pin "1") (pinfunction "1_1") (pintype "passive"))
      (node (ref "R15") (pin "1") (pinfunction "1_1") (pintype "passive"))
      (node (ref "U1") (pin "27") (pinfunction "PC4(ADC4/SDA)_27") (pintype "bidirectional"))
      (node (ref "U10") (pin "5") (pinfunction "SDA_5") (pintype "bidirectional"))
    )
    (net (code "49") (name "PC5_SCL") (class "Default")
      (node (ref "J3") (pin "13") (pinfunction "13_13") (pintype "passive"))
      (node (ref "J8") (pin "1") (pinfunction "1_1") (pintype "passive"))
      (node (ref "R14") (pin "1") (pinfunction "1_1") (pintype "passive"))
      (node (ref "U1") (pin "28") (pinfunction "PC5(ADC5/SCL)_28") (pintype "bidirectional"))
      (node (ref "U10") (pin "4") (pinfunction "SCL_4") (pintype "input"))
    )
    (net (code "50") (name "PC6_RESET") (class "Default")
      (node (ref "J10") (pin "5") (pinfunction "5_5") (pintype "passive"))
      (node (ref "J3") (pin "2") (pinfunction "2_2") (pintype "passive"))
      (node (ref "U1") (pin "29") (pinfunction "PC6(/RESET)_29") (pintype "bidirectional"))
    )
    (net (code "51") (name "PD0_RXD") (class "Default")
      (node (ref "J2") (pin "3") (pinfunction "3_3") (pintype "passive"))
      (node (ref "U1") (pin "30") (pinfunction "PD0(RXD)_30") (pintype "bidirectional"))
    )
    (net (code "52") (name "PD1_TXD") (class "Default")
      (node (ref "J2") (pin "4") (pinfunction "4_4") (pintype "passive"))
      (node (ref "U1") (pin "31") (pinfunction "PD1(TXD)_31") (pintype "bidirectional"))
    )
    (net (code "53") (name "PD2_INT0") (class "Default")
      (node (ref "J2") (pin "5") (pinfunction "5_5") (pintype "passive"))
      (node (ref "U1") (pin "32") (pinfunction "PD2(INT0)_32") (pintype "bidirectional"))
    )
    (net (code "54") (name "PD3_INT1") (class "Default")
      (node (ref "J2") (pin "6") (pinfunction "6_6") (pintype "passive"))
      (node (ref "U1") (pin "1") (pinfunction "PD3(INT1)_1") (pintype "bidirectional"))
    )
    (net (code "55") (name "PD4_XCK") (class "Default")
      (node (ref "J2") (pin "9") (pinfunction "9_9") (pintype "passive"))
      (node (ref "U1") (pin "2") (pinfunction "PD4(XCK/T0)_2") (pintype "bidirectional"))
    )
    (net (code "56") (name "PD5_T1") (class "Default")
      (node (ref "J2") (pin "10") (pinfunction "10_10") (pintype "passive"))
      (node (ref "U1") (pin "9") (pinfunction "PD5(T1)_9") (pintype "bidirectional"))
    )
    (net (code "57") (name "PD6_AIN0") (class "Default")
      (node (ref "J2") (pin "11") (pinfunction "11_11") (pintype "passive"))
      (node (ref "U1") (pin "10") (pinfunction "PD6(AIN0)_10") (pintype "bidirectional"))
    )
    (net (code "58") (name "PD7_AIN1") (class "Default")
      (node (ref "J2") (pin "12") (pinfunction "12_12") (pintype "passive"))
      (node (ref "U1") (pin "11") (pinfunction "PD7(AIN1)_11") (pintype "bidirectional"))
    )
    (net (code "59") (name "RX_RF") (class "Default")
      (node (ref "C23") (pin "1") (pinfunction "1_1") (pintype "passive"))
      (node (ref "J14") (pin "1") (pinfunction "1_1") (pintype "passive"))
      (node (ref "J2") (pin "13") (pinfunction "13_13") (pintype "passive"))
    )
    (net (code "60") (name "TO_FST") (class "Default")
      (node (ref "C1") (pin "1") (pinfunction "1_1") (pintype "passive"))
      (node (ref "Q1") (pin "2") (pinfunction "S_2") (pintype "bidirectional"))
      (node (ref "R16") (pin "2") (pinfunction "2_2") (pintype "passive"))
    )
    (net (code "61") (name "VCC") (class "Default")
      (node (ref "D1") (pin "1") (pinfunction "A_1") (pintype "passive"))
      (node (ref "J10") (pin "2") (pinfunction "2_2") (pintype "passive"))
      (node (ref "J3") (pin "6") (pinfunction "6_6") (pintype "passive"))
      (node (ref "L1") (pin "2") (pinfunction "2_2") (pintype "passive"))
      (node (ref "R22") (pin "1") (pinfunction "1_1") (pintype "passive"))
      (node (ref "R24") (pin "1") (pinfunction "1_1") (pintype "passive"))
      (node (ref "R25") (pin "1") (pinfunction "1_1") (pintype "passive"))
    )
    (net (code "62") (name "XA") (class "Default")
      (node (ref "C99") (pin "2") (pinfunction "2_2") (pintype "passive"))
      (node (ref "J7") (pin "1") (pinfunction "1_1") (pintype "passive"))
      (node (ref "U10") (pin "2") (pinfunction "XA_2") (pintype "input"))
    )
    (net (code "63") (name "XB") (class "Default")
      (node (ref "J17") (pin "1") (pinfunction "1_1") (pintype "passive"))
      (node (ref "U10") (pin "3") (pinfunction "XB_3") (pintype "input"))
    )
    (net (code "64") (name "unconnected-(D1-AC-Pad3)") (class "Default")
      (node (ref "D1") (pin "3") (pinfunction "AC_3") (pintype "passive"))
    )
    (net (code "65") (name "unconnected-(IC2-1A-Pad7)") (class "Default")
      (node (ref "IC2") (pin "7") (pinfunction "1A_7") (pintype "bidirectional"))
    )
    (net (code "66") (name "unconnected-(IC2-1B1-Pad6)") (class "Default")
      (node (ref "IC2") (pin "6") (pinfunction "1B1_6") (pintype "bidirectional"))
    )
    (net (code "67") (name "unconnected-(IC2-1B2-Pad5)") (class "Default")
      (node (ref "IC2") (pin "5") (pinfunction "1B2_5") (pintype "bidirectional"))
    )
    (net (code "68") (name "unconnected-(IC2-1B3-Pad4)") (class "Default")
      (node (ref "IC2") (pin "4") (pinfunction "1B3_4") (pintype "bidirectional"))
    )
    (net (code "69") (name "unconnected-(IC2-1B4-Pad3)") (class "Default")
      (node (ref "IC2") (pin "3") (pinfunction "1B4_3") (pintype "bidirectional"))
    )
    (net (code "70") (name "unconnected-(IC3-~{O1}-Pad6)") (class "Default")
      (node (ref "IC3") (pin "6") (pinfunction "~{O1}_6") (pintype "bidirectional"))
    )
    (net (code "71") (name "unconnected-(IC3-~{O3}-Pad8)") (class "Default")
      (node (ref "IC3") (pin "8") (pinfunction "~{O3}_8") (pintype "bidirectional"))
    )
    (net (code "72") (name "unconnected-(J1-Pad3)") (class "Default")
      (node (ref "J1") (pin "3") (pinfunction "3_3") (pintype "passive"))
    )
    (net (code "73") (name "unconnected-(U1-ADC6-Pad19)") (class "Default")
      (node (ref "U1") (pin "19") (pinfunction "ADC6_19") (pintype "bidirectional"))
    )
    (net (code "74") (name "unconnected-(U1-ADC7-Pad22)") (class "Default")
      (node (ref "U1") (pin "22") (pinfunction "ADC7_22") (pintype "bidirectional"))
    )
  )
)
